# main_1.net
KiCad netlist of a schematic drawn in EAGLE
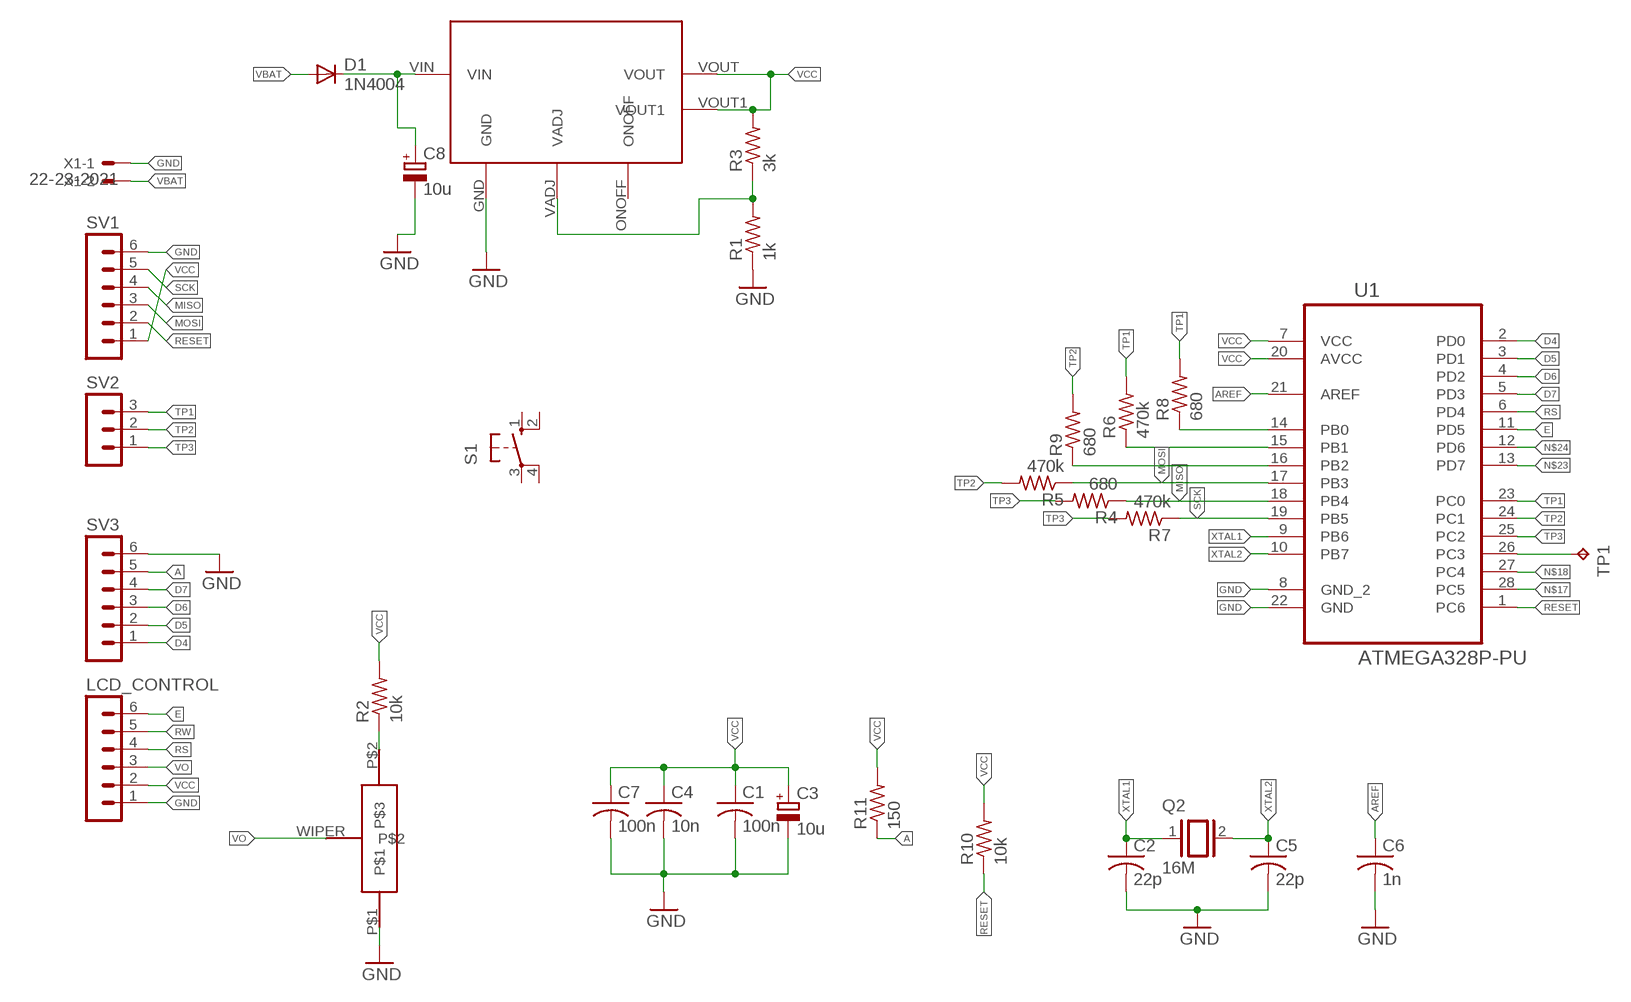
[diagram p0: schematic, sheet 1]

(export (version "E")
  (design (tool "Eeschema 10.0.6"))
  (components
    (comp (ref "C1")
      (value "100n")
      (footprint "eagle-import:C050-025X075")
      (libsource (lib "eagle-import") (part "C-US050-025X075"))
    )
    (comp (ref "C2")
      (value "22p")
      (footprint "eagle-import:C025-025X050")
      (libsource (lib "eagle-import") (part "C-US025-025X050"))
    )
    (comp (ref "C3")
      (value "10u")
      (footprint "eagle-import:E2,5-6")
      (libsource (lib "eagle-import") (part "CPOL-EUE2.5-6"))
    )
    (comp (ref "C4")
      (value "10n")
      (footprint "eagle-import:C050-025X075")
      (libsource (lib "eagle-import") (part "C-US050-025X075"))
    )
    (comp (ref "C5")
      (value "22p")
      (footprint "eagle-import:C025-025X050")
      (libsource (lib "eagle-import") (part "C-US025-025X050"))
    )
    (comp (ref "C6")
      (value "1n")
      (footprint "eagle-import:C050-025X075")
      (libsource (lib "eagle-import") (part "C-US050-025X075"))
    )
    (comp (ref "C7")
      (value "100n")
      (footprint "eagle-import:C050-025X075")
      (libsource (lib "eagle-import") (part "C-US050-025X075"))
    )
    (comp (ref "C8")
      (value "10u")
      (footprint "eagle-import:E2,5-6")
      (libsource (lib "eagle-import") (part "CPOL-EUE2.5-6"))
    )
    (comp (ref "D1")
      (value "1N4004")
      (footprint "eagle-import:DO41-10")
      (libsource (lib "eagle-import") (part "1N4004"))
    )
    (comp (ref "LCD_CONTROL")
      (value "MA06-1")
      (footprint "eagle-import:MA06-1")
      (libsource (lib "eagle-import") (part "MA06-1"))
    )
    (comp (ref "Q2")
      (value "16M")
      (footprint "eagle-import:QS")
      (libsource (lib "eagle-import") (part "XTAL/S"))
    )
    (comp (ref "R1")
      (value "1k")
      (footprint "eagle-import:0207_10")
      (libsource (lib "eagle-import") (part "R-US_0207/10"))
    )
    (comp (ref "R2")
      (value "10k")
      (footprint "eagle-import:0207_10")
      (libsource (lib "eagle-import") (part "R-US_0207/10"))
    )
    (comp (ref "R3")
      (value "3k")
      (footprint "eagle-import:0207_10")
      (libsource (lib "eagle-import") (part "R-US_0207/10"))
    )
    (comp (ref "R4")
      (value "680")
      (footprint "eagle-import:0207_10")
      (libsource (lib "eagle-import") (part "R-US_0207/10"))
    )
    (comp (ref "R5")
      (value "470k")
      (footprint "eagle-import:0207_10")
      (libsource (lib "eagle-import") (part "R-US_0207/10"))
    )
    (comp (ref "R6")
      (value "470k")
      (footprint "eagle-import:0207_10")
      (libsource (lib "eagle-import") (part "R-US_0207/10"))
    )
    (comp (ref "R7")
      (value "470k")
      (footprint "eagle-import:0207_10")
      (libsource (lib "eagle-import") (part "R-US_0207/10"))
    )
    (comp (ref "R8")
      (value "680")
      (footprint "eagle-import:0207_10")
      (libsource (lib "eagle-import") (part "R-US_0207/10"))
    )
    (comp (ref "R9")
      (value "680")
      (footprint "eagle-import:0207_10")
      (libsource (lib "eagle-import") (part "R-US_0207/10"))
    )
    (comp (ref "R10")
      (value "10k")
      (footprint "eagle-import:0207_10")
      (libsource (lib "eagle-import") (part "R-US_0207/10"))
    )
    (comp (ref "R11")
      (value "150")
      (footprint "eagle-import:0207_12")
      (libsource (lib "eagle-import") (part "R-US_0207/12"))
    )
    (comp (ref "S1")
      (value "10-XX")
      (footprint "eagle-import:B3F-10XX")
      (fields (field (name "MPN") "B3F-1000"))
      (libsource (lib "eagle-import") (part "10-XX"))
    )
    (comp (ref "SV1")
      (value "MA06-1")
      (footprint "eagle-import:MA06-1")
      (libsource (lib "eagle-import") (part "MA06-1"))
    )
    (comp (ref "SV2")
      (value "MA03-1")
      (footprint "eagle-import:MA03-1")
      (libsource (lib "eagle-import") (part "MA03-1"))
    )
    (comp (ref "SV3")
      (value "MA06-1")
      (footprint "eagle-import:MA06-1")
      (libsource (lib "eagle-import") (part "MA06-1"))
    )
    (comp (ref "TP1")
      (value "TPTP20SQ")
      (footprint "eagle-import:TP20SQ")
      (libsource (lib "eagle-import") (part "TPTP20SQ"))
    )
    (comp (ref "U$1")
      (value "POTAR")
      (footprint "eagle-import:POTAR")
      (libsource (lib "eagle-import") (part "POTAR"))
    )
    (comp (ref "U$2")
      (value "NJM2389")
      (footprint "eagle-import:DPACK-5")
      (libsource (lib "eagle-import") (part "NJM2389"))
    )
    (comp (ref "U1")
      (value "ATMEGA328P-PU")
      (footprint "eagle-import:DIP254P762X457-28")
      (libsource (lib "eagle-import") (part "ATMEGA328P-PU"))
    )
    (comp (ref "X1")
      (value "22-23-2021")
      (footprint "eagle-import:22-23-2021")
      (fields (field (name "MF") "MOLEX"))
      (libsource (lib "eagle-import") (part "22-23-2021"))
    )
  )
  (nets
    (net (code "1") (name "A") (class "Default")
      (node (ref "R11") (pin "1") (pinfunction "1_1") (pintype "passive"))
      (node (ref "SV3") (pin "5") (pinfunction "5_5") (pintype "passive"))
    )
    (net (code "2") (name "AREF") (class "Default")
      (node (ref "C6") (pin "1") (pinfunction "1_1") (pintype "passive"))
      (node (ref "U1") (pin "21") (pinfunction "AREF_21") (pintype "input"))
    )
    (net (code "3") (name "D4") (class "Default")
      (node (ref "SV3") (pin "1") (pinfunction "1_1") (pintype "passive"))
      (node (ref "U1") (pin "2") (pinfunction "PD0_2") (pintype "bidirectional"))
    )
    (net (code "4") (name "D5") (class "Default")
      (node (ref "SV3") (pin "2") (pinfunction "2_2") (pintype "passive"))
      (node (ref "U1") (pin "3") (pinfunction "PD1_3") (pintype "bidirectional"))
    )
    (net (code "5") (name "D6") (class "Default")
      (node (ref "SV3") (pin "3") (pinfunction "3_3") (pintype "passive"))
      (node (ref "U1") (pin "4") (pinfunction "PD2_4") (pintype "bidirectional"))
    )
    (net (code "6") (name "D7") (class "Default")
      (node (ref "SV3") (pin "4") (pinfunction "4_4") (pintype "passive"))
      (node (ref "U1") (pin "5") (pinfunction "PD3_5") (pintype "bidirectional"))
    )
    (net (code "7") (name "E") (class "Default")
      (node (ref "LCD_CONTROL") (pin "6") (pinfunction "6_6") (pintype "passive"))
      (node (ref "U1") (pin "11") (pinfunction "PD5_11") (pintype "bidirectional"))
    )
    (net (code "8") (name "GND") (class "Default")
      (node (ref "C1") (pin "2") (pinfunction "2_2") (pintype "passive"))
      (node (ref "C2") (pin "2") (pinfunction "2_2") (pintype "passive"))
      (node (ref "C3") (pin "-") (pinfunction "-_-") (pintype "passive"))
      (node (ref "C4") (pin "2") (pinfunction "2_2") (pintype "passive"))
      (node (ref "C5") (pin "2") (pinfunction "2_2") (pintype "passive"))
      (node (ref "C6") (pin "2") (pinfunction "2_2") (pintype "passive"))
      (node (ref "C7") (pin "2") (pinfunction "2_2") (pintype "passive"))
      (node (ref "C8") (pin "-") (pinfunction "-_-") (pintype "passive"))
      (node (ref "LCD_CONTROL") (pin "1") (pinfunction "1_1") (pintype "passive"))
      (node (ref "R1") (pin "1") (pinfunction "1_1") (pintype "passive"))
      (node (ref "SV1") (pin "6") (pinfunction "6_6") (pintype "passive"))
      (node (ref "SV3") (pin "6") (pinfunction "6_6") (pintype "passive"))
      (node (ref "U$1") (pin "P$1") (pinfunction "P$1_P$1") (pintype "bidirectional"))
      (node (ref "U$2") (pin "GND") (pinfunction "GND_GND") (pintype "bidirectional"))
      (node (ref "U1") (pin "22") (pinfunction "GND_22") (pintype "passive"))
      (node (ref "U1") (pin "8") (pinfunction "GND_2_8") (pintype "passive"))
      (node (ref "X1") (pin "1") (pinfunction "S_1") (pintype "passive"))
    )
    (net (code "9") (name "MISO") (class "Default")
      (node (ref "R4") (pin "1") (pinfunction "1_1") (pintype "passive"))
      (node (ref "SV1") (pin "4") (pinfunction "4_4") (pintype "passive"))
      (node (ref "U1") (pin "18") (pinfunction "PB4_18") (pintype "bidirectional"))
    )
    (net (code "10") (name "MOSI") (class "Default")
      (node (ref "R5") (pin "1") (pinfunction "1_1") (pintype "passive"))
      (node (ref "SV1") (pin "3") (pinfunction "3_3") (pintype "passive"))
      (node (ref "U1") (pin "17") (pinfunction "PB3_17") (pintype "bidirectional"))
    )
    (net (code "11") (name "N$17") (class "Default")
      (node (ref "U1") (pin "28") (pinfunction "PC5_28") (pintype "bidirectional"))
    )
    (net (code "12") (name "N$18") (class "Default")
      (node (ref "U1") (pin "27") (pinfunction "PC4_27") (pintype "bidirectional"))
    )
    (net (code "13") (name "N$23") (class "Default")
      (node (ref "U1") (pin "13") (pinfunction "PD7_13") (pintype "bidirectional"))
    )
    (net (code "14") (name "N$24") (class "Default")
      (node (ref "U1") (pin "12") (pinfunction "PD6_12") (pintype "bidirectional"))
    )
    (net (code "15") (name "Net-(C8-Pad+)") (class "Default")
      (node (ref "C8") (pin "+") (pinfunction "+_+") (pintype "passive"))
      (node (ref "D1") (pin "C") (pinfunction "C_C") (pintype "passive"))
      (node (ref "U$2") (pin "VIN") (pinfunction "VIN_VIN") (pintype "bidirectional"))
    )
    (net (code "16") (name "Net-(R1-Pad2)") (class "Default")
      (node (ref "R1") (pin "2") (pinfunction "2_2") (pintype "passive"))
      (node (ref "R3") (pin "1") (pinfunction "1_1") (pintype "passive"))
      (node (ref "U$2") (pin "VADJ") (pinfunction "VADJ_VADJ") (pintype "bidirectional"))
    )
    (net (code "17") (name "Net-(U$1-P$3)") (class "Default")
      (node (ref "R2") (pin "1") (pinfunction "1_1") (pintype "passive"))
      (node (ref "U$1") (pin "P$2") (pinfunction "P$3_P$2") (pintype "bidirectional"))
    )
    (net (code "18") (name "Net-(U1-PB0)") (class "Default")
      (node (ref "R8") (pin "1") (pinfunction "1_1") (pintype "passive"))
      (node (ref "U1") (pin "14") (pinfunction "PB0_14") (pintype "bidirectional"))
    )
    (net (code "19") (name "Net-(U1-PB1)") (class "Default")
      (node (ref "R6") (pin "1") (pinfunction "1_1") (pintype "passive"))
      (node (ref "U1") (pin "15") (pinfunction "PB1_15") (pintype "bidirectional"))
    )
    (net (code "20") (name "Net-(U1-PB2)") (class "Default")
      (node (ref "R9") (pin "1") (pinfunction "1_1") (pintype "passive"))
      (node (ref "U1") (pin "16") (pinfunction "PB2_16") (pintype "bidirectional"))
    )
    (net (code "21") (name "Net-(U1-PC3)") (class "Default")
      (node (ref "TP1") (pin "TP") (pinfunction "TP_TP") (pintype "input"))
      (node (ref "U1") (pin "26") (pinfunction "PC3_26") (pintype "bidirectional"))
    )
    (net (code "22") (name "RESET") (class "Default")
      (node (ref "R10") (pin "1") (pinfunction "1_1") (pintype "passive"))
      (node (ref "SV1") (pin "2") (pinfunction "2_2") (pintype "passive"))
      (node (ref "U1") (pin "1") (pinfunction "PC6_1") (pintype "bidirectional"))
    )
    (net (code "23") (name "RS") (class "Default")
      (node (ref "LCD_CONTROL") (pin "4") (pinfunction "4_4") (pintype "passive"))
      (node (ref "U1") (pin "6") (pinfunction "PD4_6") (pintype "bidirectional"))
    )
    (net (code "24") (name "RW") (class "Default")
      (node (ref "LCD_CONTROL") (pin "5") (pinfunction "5_5") (pintype "passive"))
    )
    (net (code "25") (name "SCK") (class "Default")
      (node (ref "R7") (pin "1") (pinfunction "1_1") (pintype "passive"))
      (node (ref "SV1") (pin "5") (pinfunction "5_5") (pintype "passive"))
      (node (ref "U1") (pin "19") (pinfunction "PB5_19") (pintype "bidirectional"))
    )
    (net (code "26") (name "TP1") (class "Default")
      (node (ref "R6") (pin "2") (pinfunction "2_2") (pintype "passive"))
      (node (ref "R8") (pin "2") (pinfunction "2_2") (pintype "passive"))
      (node (ref "SV2") (pin "3") (pinfunction "3_3") (pintype "passive"))
      (node (ref "U1") (pin "23") (pinfunction "PC0_23") (pintype "bidirectional"))
    )
    (net (code "27") (name "TP2") (class "Default")
      (node (ref "R5") (pin "2") (pinfunction "2_2") (pintype "passive"))
      (node (ref "R9") (pin "2") (pinfunction "2_2") (pintype "passive"))
      (node (ref "SV2") (pin "2") (pinfunction "2_2") (pintype "passive"))
      (node (ref "U1") (pin "24") (pinfunction "PC1_24") (pintype "bidirectional"))
    )
    (net (code "28") (name "TP3") (class "Default")
      (node (ref "R4") (pin "2") (pinfunction "2_2") (pintype "passive"))
      (node (ref "R7") (pin "2") (pinfunction "2_2") (pintype "passive"))
      (node (ref "SV2") (pin "1") (pinfunction "1_1") (pintype "passive"))
      (node (ref "U1") (pin "25") (pinfunction "PC2_25") (pintype "bidirectional"))
    )
    (net (code "29") (name "VBAT") (class "Default")
      (node (ref "D1") (pin "A") (pinfunction "A_A") (pintype "passive"))
      (node (ref "X1") (pin "2") (pinfunction "S_2") (pintype "passive"))
    )
    (net (code "30") (name "VCC") (class "Default")
      (node (ref "C1") (pin "1") (pinfunction "1_1") (pintype "passive"))
      (node (ref "C3") (pin "+") (pinfunction "+_+") (pintype "passive"))
      (node (ref "C4") (pin "1") (pinfunction "1_1") (pintype "passive"))
      (node (ref "C7") (pin "1") (pinfunction "1_1") (pintype "passive"))
      (node (ref "LCD_CONTROL") (pin "2") (pinfunction "2_2") (pintype "passive"))
      (node (ref "R10") (pin "2") (pinfunction "2_2") (pintype "passive"))
      (node (ref "R11") (pin "2") (pinfunction "2_2") (pintype "passive"))
      (node (ref "R2") (pin "2") (pinfunction "2_2") (pintype "passive"))
      (node (ref "R3") (pin "2") (pinfunction "2_2") (pintype "passive"))
      (node (ref "SV1") (pin "1") (pinfunction "1_1") (pintype "passive"))
      (node (ref "U$2") (pin "VOUT") (pinfunction "VOUT_VOUT") (pintype "bidirectional"))
      (node (ref "U$2") (pin "VOUT1") (pinfunction "VOUT1_VOUT1") (pintype "bidirectional"))
      (node (ref "U1") (pin "20") (pinfunction "AVCC_20") (pintype "power_in"))
      (node (ref "U1") (pin "7") (pinfunction "VCC_7") (pintype "power_in"))
    )
    (net (code "31") (name "VO") (class "Default")
      (node (ref "LCD_CONTROL") (pin "3") (pinfunction "3_3") (pintype "passive"))
      (node (ref "U$1") (pin "WIPER") (pinfunction "P$2_WIPER") (pintype "bidirectional"))
    )
    (net (code "32") (name "XTAL1") (class "Default")
      (node (ref "C2") (pin "1") (pinfunction "1_1") (pintype "passive"))
      (node (ref "Q2") (pin "1") (pinfunction "1_1") (pintype "passive"))
      (node (ref "U1") (pin "9") (pinfunction "PB6_9") (pintype "bidirectional"))
    )
    (net (code "33") (name "XTAL2") (class "Default")
      (node (ref "C5") (pin "1") (pinfunction "1_1") (pintype "passive"))
      (node (ref "Q2") (pin "2") (pinfunction "2_2") (pintype "passive"))
      (node (ref "U1") (pin "10") (pinfunction "PB7_10") (pintype "bidirectional"))
    )
    (net (code "34") (name "unconnected-(S1-P-Pad3)") (class "Default")
      (node (ref "S1") (pin "3") (pinfunction "P_3") (pintype "passive"))
    )
    (net (code "35") (name "unconnected-(S1-P1-Pad4)") (class "Default")
      (node (ref "S1") (pin "4") (pinfunction "P1_4") (pintype "passive"))
    )
    (net (code "36") (name "unconnected-(S1-S-Pad1)") (class "Default")
      (node (ref "S1") (pin "1") (pinfunction "S_1") (pintype "passive"))
    )
    (net (code "37") (name "unconnected-(S1-S1-Pad2)") (class "Default")
      (node (ref "S1") (pin "2") (pinfunction "S1_2") (pintype "passive"))
    )
    (net (code "38") (name "unconnected-(U$2-PadONOFF)") (class "Default")
      (node (ref "U$2") (pin "ONOFF") (pinfunction "ONOFF_ONOFF") (pintype "bidirectional"))
    )
  )
)
